# Pico_26Pin_FPC_Adapter.net
KiCad netlist of a schematic drawn in EAGLE
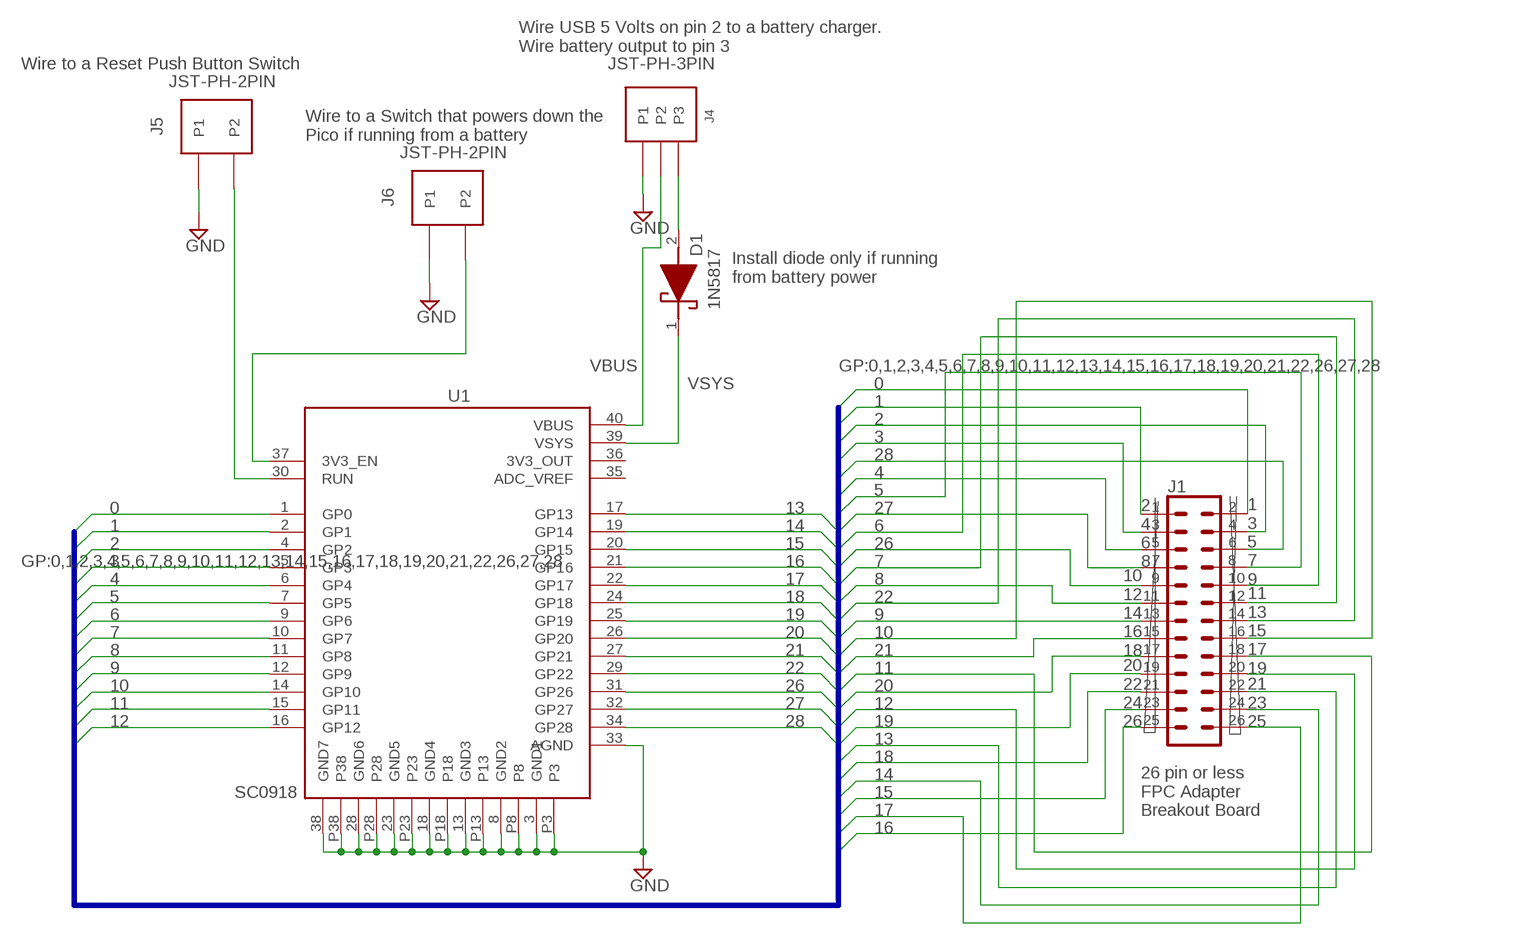
[diagram p0: schematic, sheet 1]

(export (version "E")
  (design (tool "Eeschema 10.0.6"))
  (components
    (comp (ref "D1")
      (value "1N5817")
      (footprint "eagle-import:DIOAD1410W86L470D235")
      (fields (field (name "MOUSER_PART_NUMBER") "821-1N5817"))
      (libsource (lib "eagle-import") (part "1N5817"))
    )
    (comp (ref "J1")
      (value "CONN_13X22X13")
      (footprint "eagle-import:2X13")
      (libsource (lib "eagle-import") (part "CONN_13X22X13"))
    )
    (comp (ref "J4")
      (value "JST-PH-3PIN")
      (footprint "eagle-import:JST-PH-3PIN")
      (libsource (lib "eagle-import") (part "JST-PH-3PIN"))
    )
    (comp (ref "J5")
      (value "JST-PH-2PIN")
      (footprint "eagle-import:JST-PH-2PIN")
      (libsource (lib "eagle-import") (part "JST-PH-2PIN"))
    )
    (comp (ref "J6")
      (value "JST-PH-2PIN")
      (footprint "eagle-import:JST-PH-2PIN")
      (libsource (lib "eagle-import") (part "JST-PH-2PIN"))
    )
    (comp (ref "U1")
      (value "SC0918")
      (footprint "eagle-import:MODULE_SC0918")
      (fields (field (name "MF") "Raspberry Pi"))
      (libsource (lib "eagle-import") (part "SC0918"))
    )
  )
  (nets
    (net (code "2") (name "/0") (class "Default")
      (node (ref "J1") (pin "2") (pinfunction "2_2") (pintype "passive"))
      (node (ref "U1") (pin "1") (pinfunction "GP0_1") (pintype "bidirectional"))
    )
    (net (code "3") (name "/1") (class "Default")
      (node (ref "J1") (pin "1") (pinfunction "1_1") (pintype "passive"))
      (node (ref "U1") (pin "2") (pinfunction "GP1_2") (pintype "bidirectional"))
    )
    (net (code "4") (name "/2") (class "Default")
      (node (ref "J1") (pin "4") (pinfunction "4_4") (pintype "passive"))
      (node (ref "U1") (pin "4") (pinfunction "GP2_4") (pintype "bidirectional"))
    )
    (net (code "5") (name "/3") (class "Default")
      (node (ref "J1") (pin "3") (pinfunction "3_3") (pintype "passive"))
      (node (ref "U1") (pin "5") (pinfunction "GP3_5") (pintype "bidirectional"))
    )
    (net (code "6") (name "/3V3_OUT") (class "Default")
      (node (ref "U1") (pin "36") (pinfunction "3V3_OUT_36") (pintype "power_in"))
    )
    (net (code "7") (name "/4") (class "Default")
      (node (ref "J1") (pin "5") (pinfunction "5_5") (pintype "passive"))
      (node (ref "U1") (pin "6") (pinfunction "GP4_6") (pintype "bidirectional"))
    )
    (net (code "8") (name "/5") (class "Default")
      (node (ref "J1") (pin "8") (pinfunction "8_8") (pintype "passive"))
      (node (ref "U1") (pin "7") (pinfunction "GP5_7") (pintype "bidirectional"))
    )
    (net (code "9") (name "/6") (class "Default")
      (node (ref "J1") (pin "10") (pinfunction "10_10") (pintype "passive"))
      (node (ref "U1") (pin "9") (pinfunction "GP6_9") (pintype "bidirectional"))
    )
    (net (code "10") (name "/7") (class "Default")
      (node (ref "J1") (pin "12") (pinfunction "12_12") (pintype "passive"))
      (node (ref "U1") (pin "10") (pinfunction "GP7_10") (pintype "bidirectional"))
    )
    (net (code "11") (name "/8") (class "Default")
      (node (ref "J1") (pin "11") (pinfunction "11_11") (pintype "passive"))
      (node (ref "U1") (pin "11") (pinfunction "GP8_11") (pintype "bidirectional"))
    )
    (net (code "12") (name "/9") (class "Default")
      (node (ref "J1") (pin "13") (pinfunction "13_13") (pintype "passive"))
      (node (ref "U1") (pin "12") (pinfunction "GP9_12") (pintype "bidirectional"))
    )
    (net (code "13") (name "/10") (class "Default")
      (node (ref "J1") (pin "16") (pinfunction "16_16") (pintype "passive"))
      (node (ref "U1") (pin "14") (pinfunction "GP10_14") (pintype "bidirectional"))
    )
    (net (code "14") (name "/11") (class "Default")
      (node (ref "J1") (pin "18") (pinfunction "18_18") (pintype "passive"))
      (node (ref "U1") (pin "15") (pinfunction "GP11_15") (pintype "bidirectional"))
    )
    (net (code "15") (name "/12") (class "Default")
      (node (ref "J1") (pin "20") (pinfunction "20_20") (pintype "passive"))
      (node (ref "U1") (pin "16") (pinfunction "GP12_16") (pintype "bidirectional"))
    )
    (net (code "16") (name "/13") (class "Default")
      (node (ref "J1") (pin "22") (pinfunction "22_22") (pintype "passive"))
      (node (ref "U1") (pin "17") (pinfunction "GP13_17") (pintype "bidirectional"))
    )
    (net (code "17") (name "/14") (class "Default")
      (node (ref "J1") (pin "24") (pinfunction "24_24") (pintype "passive"))
      (node (ref "U1") (pin "19") (pinfunction "GP14_19") (pintype "bidirectional"))
    )
    (net (code "18") (name "/15") (class "Default")
      (node (ref "J1") (pin "23") (pinfunction "23_23") (pintype "passive"))
      (node (ref "U1") (pin "20") (pinfunction "GP15_20") (pintype "bidirectional"))
    )
    (net (code "19") (name "/16") (class "Default")
      (node (ref "J1") (pin "25") (pinfunction "25_25") (pintype "passive"))
      (node (ref "U1") (pin "21") (pinfunction "GP16_21") (pintype "bidirectional"))
    )
    (net (code "20") (name "/17") (class "Default")
      (node (ref "J1") (pin "26") (pinfunction "26_26") (pintype "passive"))
      (node (ref "U1") (pin "22") (pinfunction "GP17_22") (pintype "bidirectional"))
    )
    (net (code "21") (name "/18") (class "Default")
      (node (ref "J1") (pin "21") (pinfunction "21_21") (pintype "passive"))
      (node (ref "U1") (pin "24") (pinfunction "GP18_24") (pintype "bidirectional"))
    )
    (net (code "22") (name "/19") (class "Default")
      (node (ref "J1") (pin "19") (pinfunction "19_19") (pintype "passive"))
      (node (ref "U1") (pin "25") (pinfunction "GP19_25") (pintype "bidirectional"))
    )
    (net (code "23") (name "/20") (class "Default")
      (node (ref "J1") (pin "17") (pinfunction "17_17") (pintype "passive"))
      (node (ref "U1") (pin "26") (pinfunction "GP20_26") (pintype "bidirectional"))
    )
    (net (code "24") (name "/21") (class "Default")
      (node (ref "J1") (pin "15") (pinfunction "15_15") (pintype "passive"))
      (node (ref "U1") (pin "27") (pinfunction "GP21_27") (pintype "bidirectional"))
    )
    (net (code "25") (name "/22") (class "Default")
      (node (ref "J1") (pin "14") (pinfunction "14_14") (pintype "passive"))
      (node (ref "U1") (pin "29") (pinfunction "GP22_29") (pintype "bidirectional"))
    )
    (net (code "26") (name "/26") (class "Default")
      (node (ref "J1") (pin "9") (pinfunction "9_9") (pintype "passive"))
      (node (ref "U1") (pin "31") (pinfunction "GP26_31") (pintype "bidirectional"))
    )
    (net (code "27") (name "/27") (class "Default")
      (node (ref "J1") (pin "7") (pinfunction "7_7") (pintype "passive"))
      (node (ref "U1") (pin "32") (pinfunction "GP27_32") (pintype "bidirectional"))
    )
    (net (code "28") (name "/28") (class "Default")
      (node (ref "J1") (pin "6") (pinfunction "6_6") (pintype "passive"))
      (node (ref "U1") (pin "34") (pinfunction "GP28_34") (pintype "bidirectional"))
    )
    (net (code "29") (name "/ADC_VREF") (class "Default")
      (node (ref "U1") (pin "35") (pinfunction "ADC_VREF_35") (pintype "power_in"))
    )
    (net (code "30") (name "/VBUS") (class "Default")
      (node (ref "J4") (pin "P$2") (pinfunction "P2_P$2") (pintype "bidirectional"))
      (node (ref "U1") (pin "40") (pinfunction "VBUS_40") (pintype "power_in"))
    )
    (net (code "31") (name "/VSYS") (class "Default")
      (node (ref "D1") (pin "1") (pinfunction "K_1") (pintype "bidirectional"))
      (node (ref "U1") (pin "39") (pinfunction "VSYS_39") (pintype "power_in"))
    )
    (net (code "33") (name "GND") (class "Default")
      (node (ref "J4") (pin "P$1") (pinfunction "P1_P$1") (pintype "bidirectional"))
      (node (ref "J5") (pin "P$1") (pinfunction "P1_P$1") (pintype "bidirectional"))
      (node (ref "J6") (pin "P$1") (pinfunction "P1_P$1") (pintype "bidirectional"))
      (node (ref "U1") (pin "13") (pinfunction "GND3_13") (pintype "power_in"))
      (node (ref "U1") (pin "18") (pinfunction "GND4_18") (pintype "power_in"))
      (node (ref "U1") (pin "23") (pinfunction "GND5_23") (pintype "power_in"))
      (node (ref "U1") (pin "28") (pinfunction "GND6_28") (pintype "power_in"))
      (node (ref "U1") (pin "3") (pinfunction "GND1_3") (pintype "power_in"))
      (node (ref "U1") (pin "33") (pinfunction "AGND_33") (pintype "power_in"))
      (node (ref "U1") (pin "38") (pinfunction "GND7_38") (pintype "power_in"))
      (node (ref "U1") (pin "8") (pinfunction "GND2_8") (pintype "power_in"))
      (node (ref "U1") (pin "P13") (pinfunction "P13_P13") (pintype "power_in"))
      (node (ref "U1") (pin "P18") (pinfunction "P18_P18") (pintype "power_in"))
      (node (ref "U1") (pin "P23") (pinfunction "P23_P23") (pintype "power_in"))
      (node (ref "U1") (pin "P28") (pinfunction "P28_P28") (pintype "power_in"))
      (node (ref "U1") (pin "P3") (pinfunction "P3_P3") (pintype "power_in"))
      (node (ref "U1") (pin "P38") (pinfunction "P38_P38") (pintype "power_in"))
      (node (ref "U1") (pin "P8") (pinfunction "P8_P8") (pintype "power_in"))
    )
    (net (code "34") (name "Net-(D1-A)") (class "Default")
      (node (ref "D1") (pin "2") (pinfunction "A_2") (pintype "bidirectional"))
      (node (ref "J4") (pin "P$3") (pinfunction "P3_P$3") (pintype "bidirectional"))
    )
    (net (code "35") (name "Net-(J5-P2)") (class "Default")
      (node (ref "J5") (pin "P$2") (pinfunction "P2_P$2") (pintype "bidirectional"))
      (node (ref "U1") (pin "30") (pinfunction "RUN_30") (pintype "input"))
    )
    (net (code "36") (name "Net-(J6-P2)") (class "Default")
      (node (ref "J6") (pin "P$2") (pinfunction "P2_P$2") (pintype "bidirectional"))
      (node (ref "U1") (pin "37") (pinfunction "3V3_EN_37") (pintype "input"))
    )
  )
)
